# ProPrj_Volt_Meter_25_3_25_2025-04-11.net
KiCad netlist of a schematic drawn in EasyEDA Pro
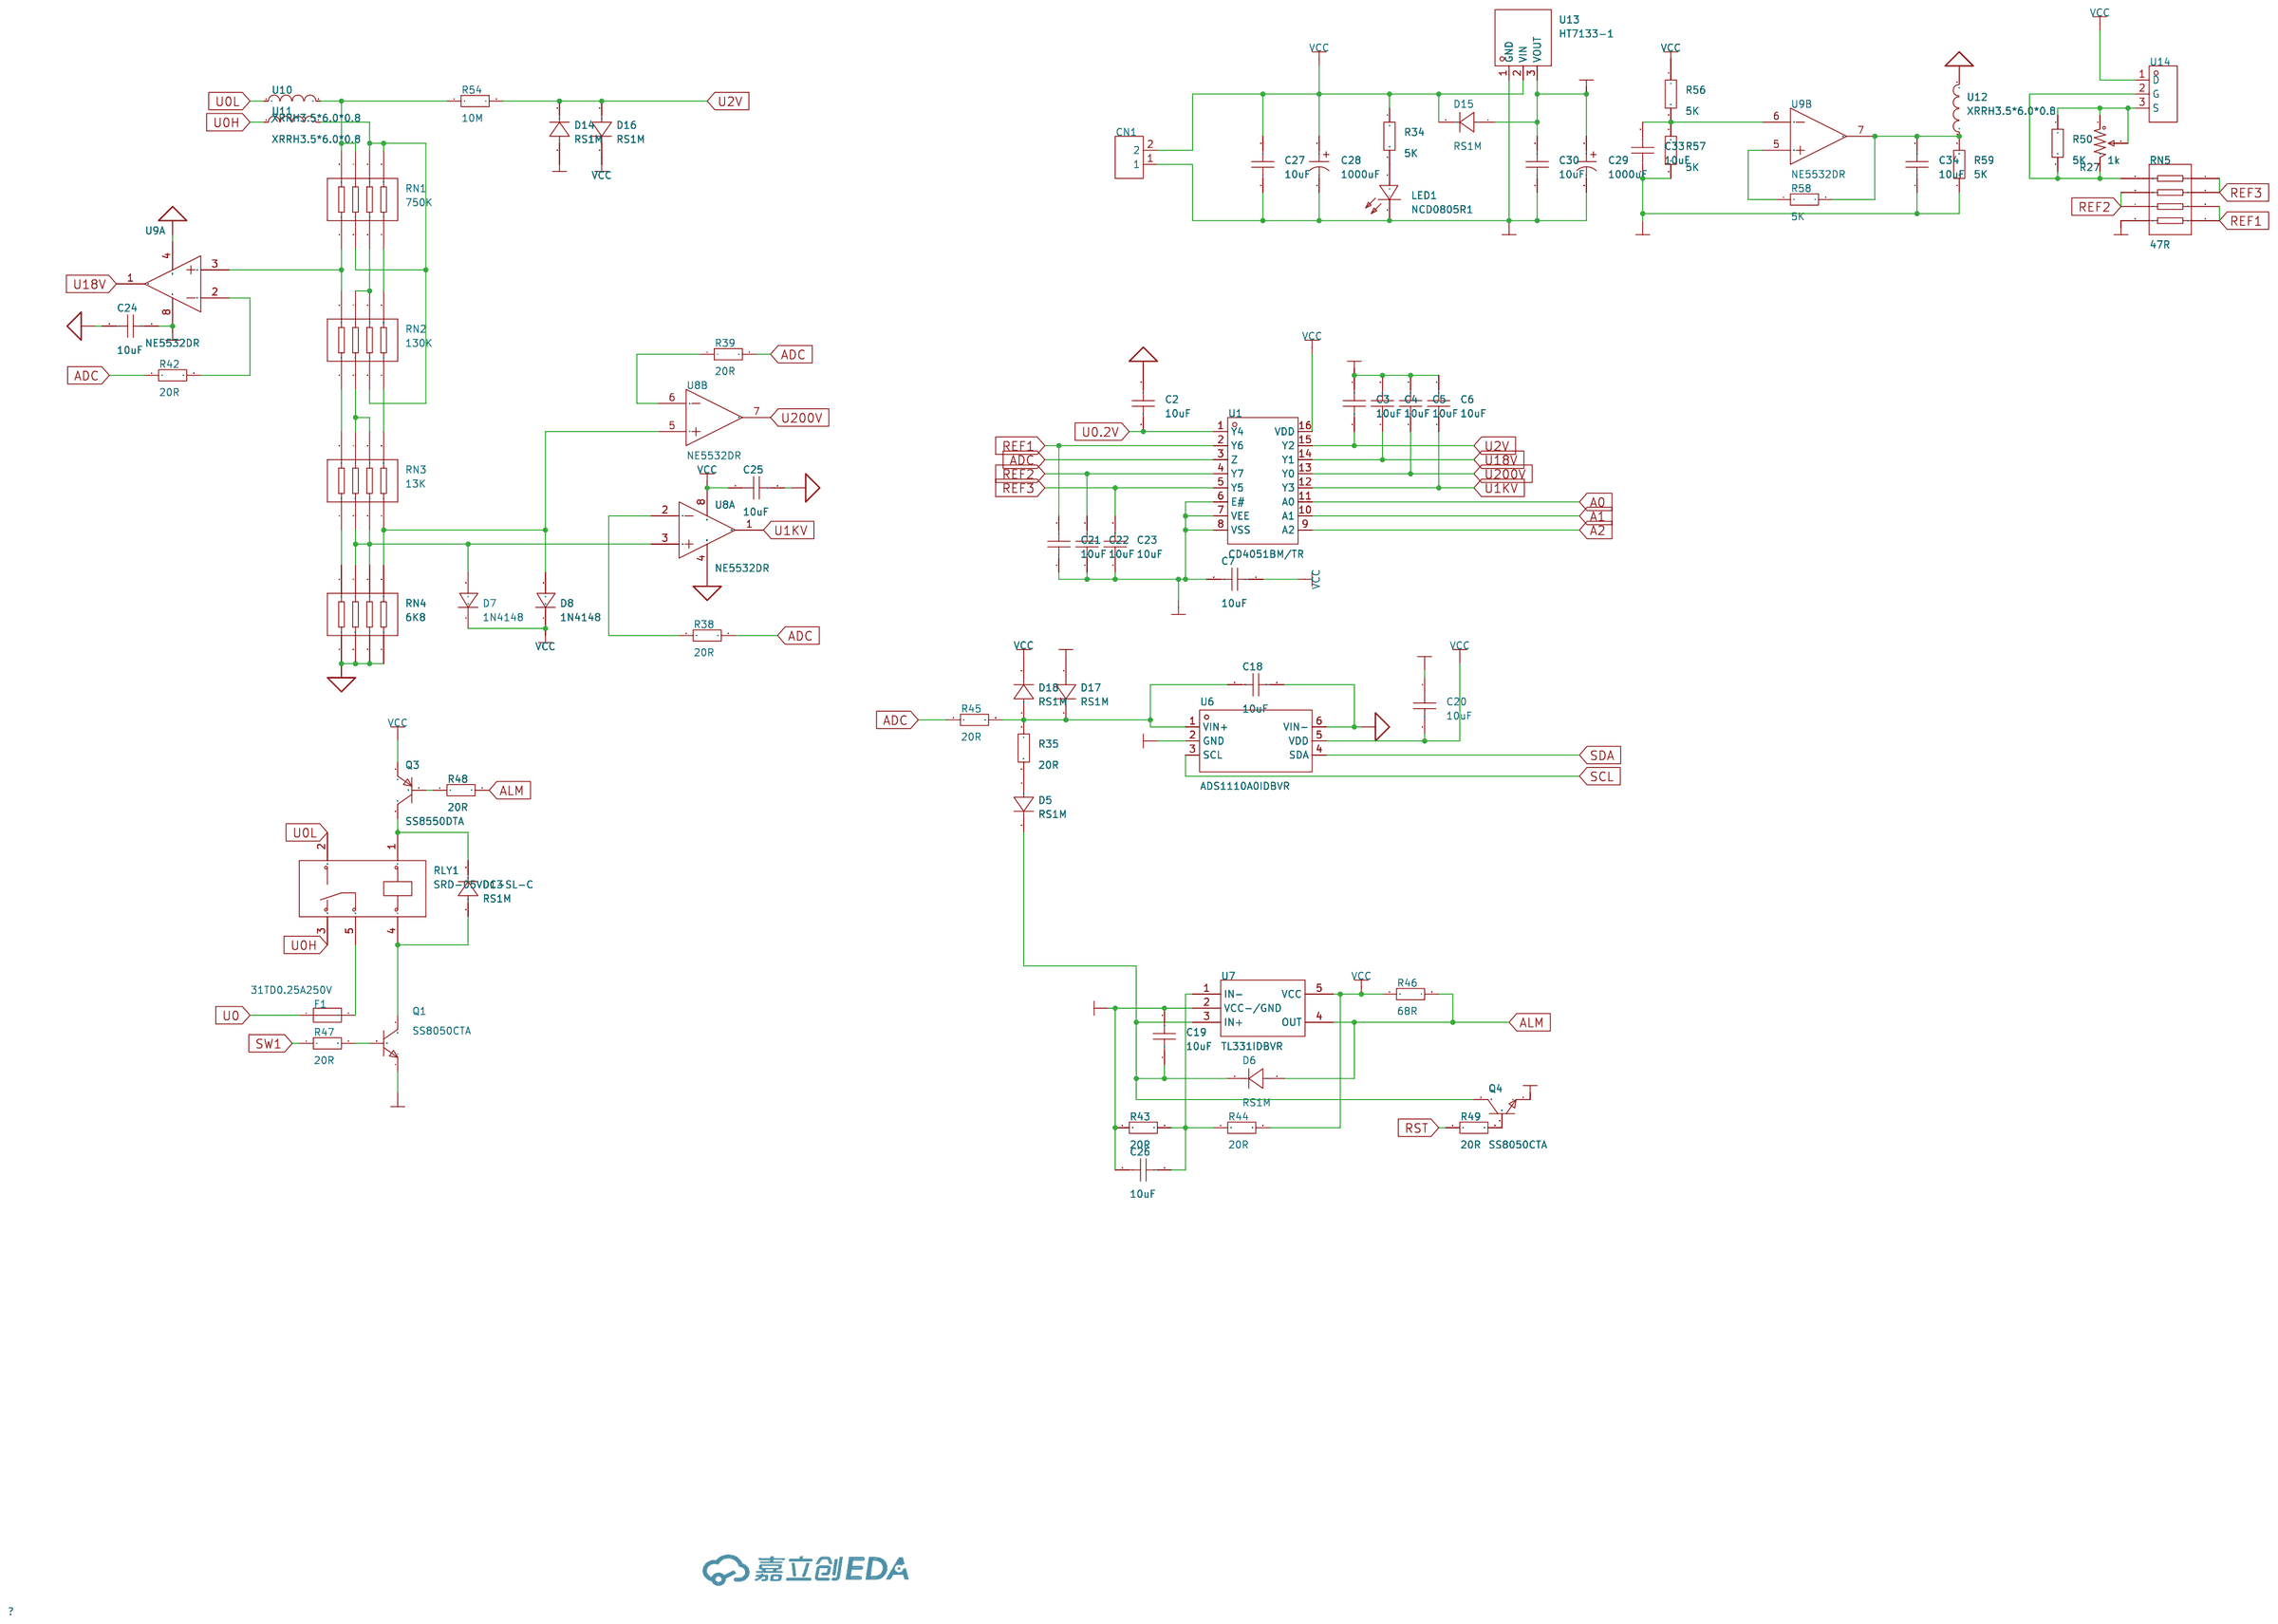
[diagram p0: P1]
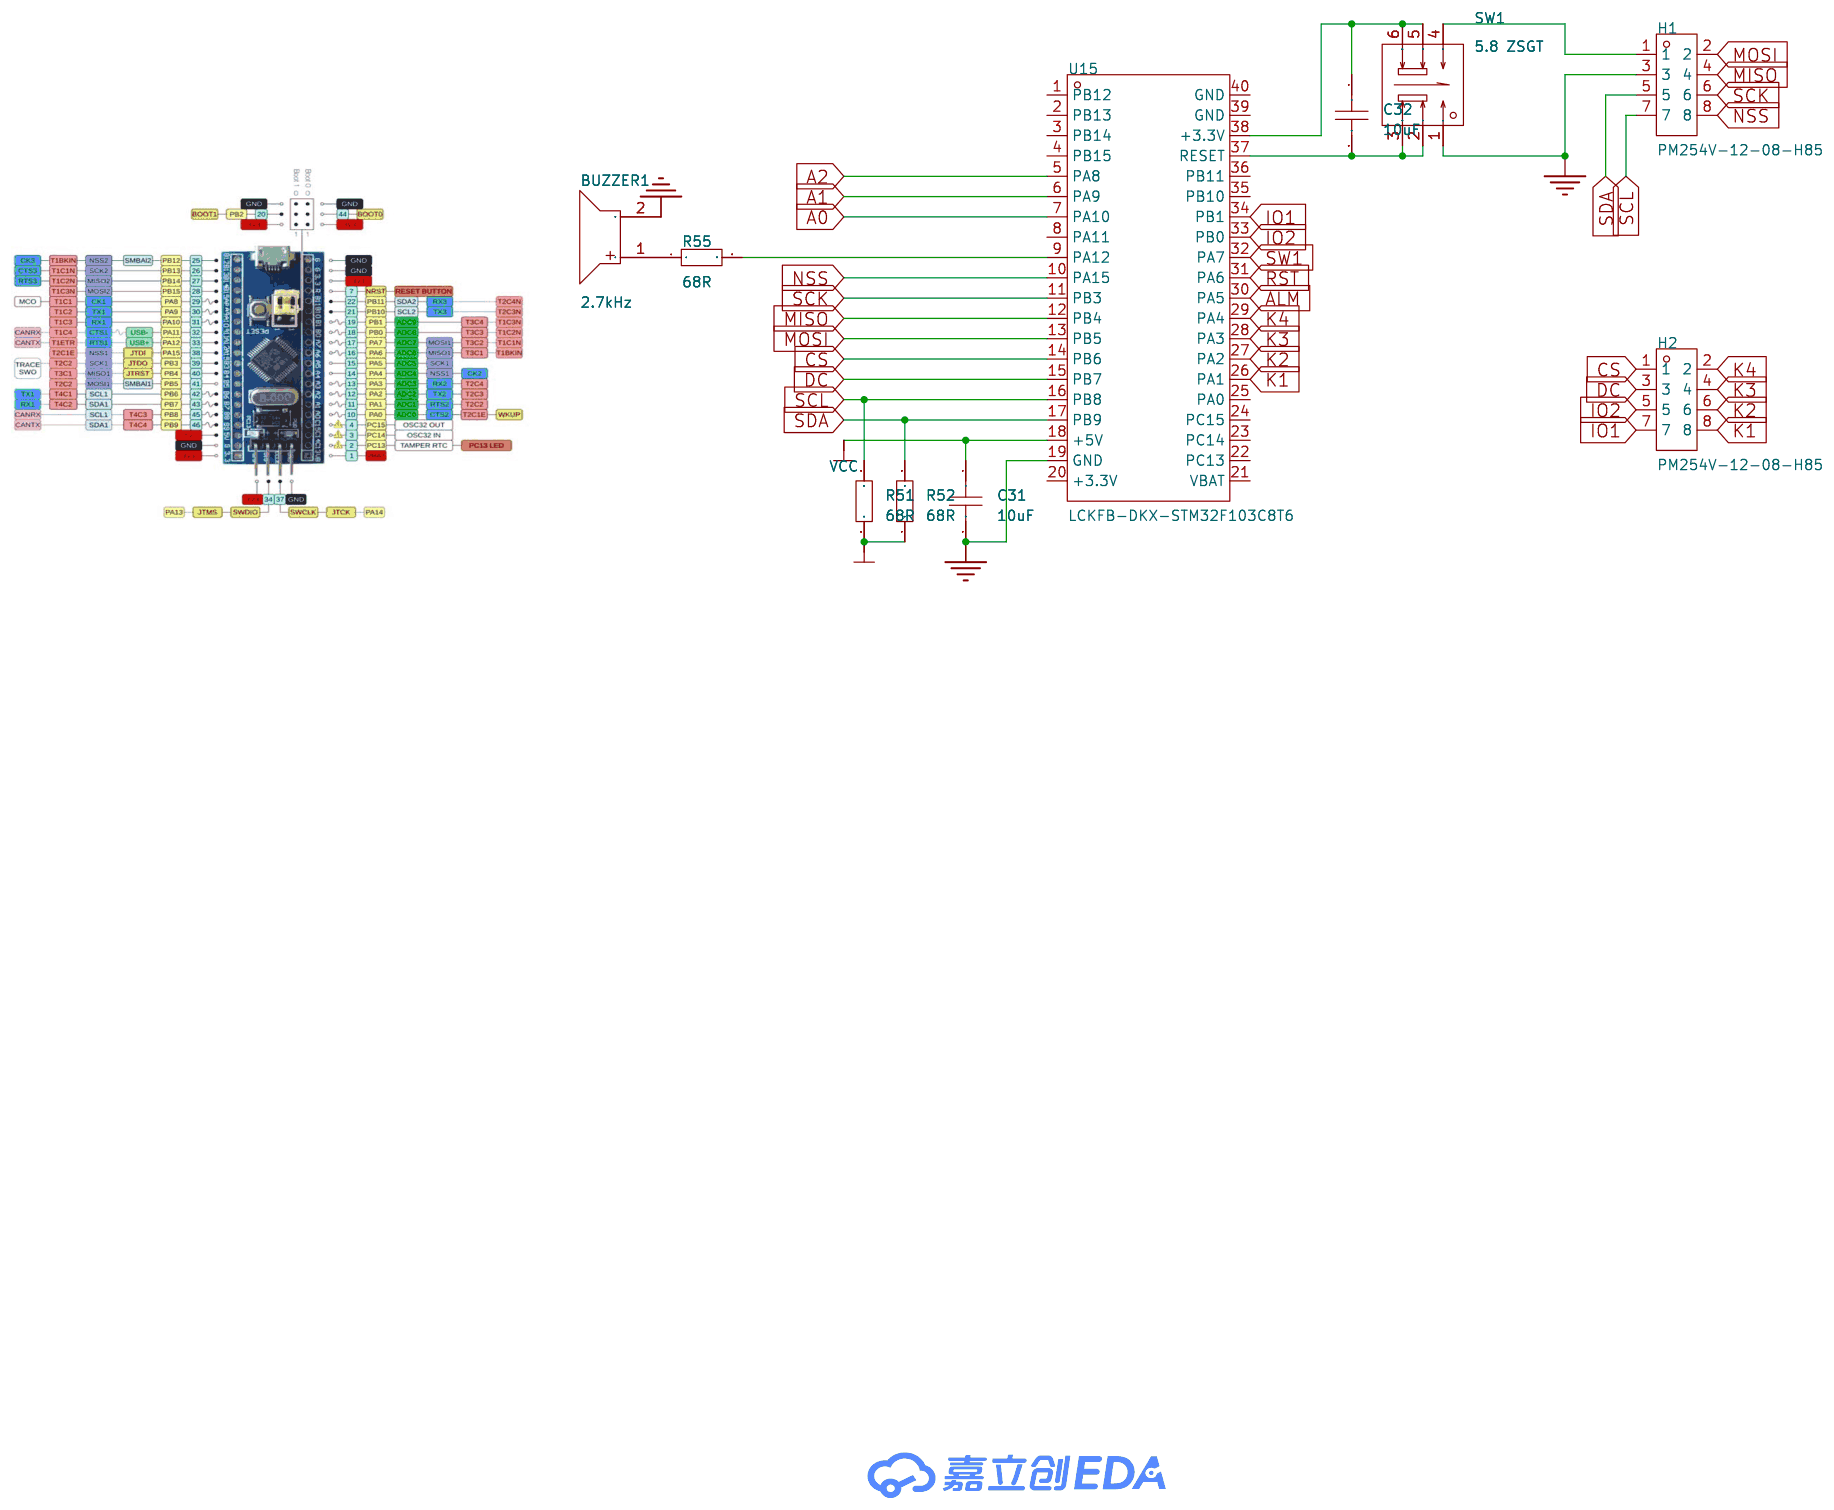
[diagram p1: P2]

(export (version "E")
  (design (tool "Eeschema 10.0.6"))
  (components
    (comp (ref "C2")
      (value "10uF")
      (footprint "easyedapro:C1206")
      (description "容值:10uF;精度:±10%;额定电压:50V;温度系数:X5R;")
      (fields
        (field (name "Manufacturer Part") "HGC1206R5106K500NSPJ")
        (field (name "Manufacturer") "Chinocera(华瓷)")
      )
      (libsource (lib "easyedapro") (part "HGC1206R5106K500NSPJ"))
    )
    (comp (ref "C3")
      (value "10uF")
      (footprint "easyedapro:C1206")
      (description "容值:10uF;精度:±10%;额定电压:50V;温度系数:X5R;")
      (fields
        (field (name "Manufacturer Part") "HGC1206R5106K500NSPJ")
        (field (name "Manufacturer") "Chinocera(华瓷)")
      )
      (libsource (lib "easyedapro") (part "HGC1206R5106K500NSPJ"))
    )
    (comp (ref "C4")
      (value "10uF")
      (footprint "easyedapro:C1206")
      (description "容值:10uF;精度:±10%;额定电压:50V;温度系数:X5R;")
      (fields
        (field (name "Manufacturer Part") "HGC1206R5106K500NSPJ")
        (field (name "Manufacturer") "Chinocera(华瓷)")
      )
      (libsource (lib "easyedapro") (part "HGC1206R5106K500NSPJ"))
    )
    (comp (ref "C5")
      (value "10uF")
      (footprint "easyedapro:C1206")
      (description "容值:10uF;精度:±10%;额定电压:50V;温度系数:X5R;")
      (fields
        (field (name "Manufacturer Part") "HGC1206R5106K500NSPJ")
        (field (name "Manufacturer") "Chinocera(华瓷)")
      )
      (libsource (lib "easyedapro") (part "HGC1206R5106K500NSPJ"))
    )
    (comp (ref "C6")
      (value "10uF")
      (footprint "easyedapro:C1206")
      (description "容值:10uF;精度:±10%;额定电压:50V;温度系数:X5R;")
      (fields
        (field (name "Manufacturer Part") "HGC1206R5106K500NSPJ")
        (field (name "Manufacturer") "Chinocera(华瓷)")
      )
      (libsource (lib "easyedapro") (part "HGC1206R5106K500NSPJ"))
    )
    (comp (ref "C7")
      (value "10uF")
      (footprint "easyedapro:C1206")
      (description "容值:10uF;精度:±10%;额定电压:50V;温度系数:X5R;")
      (fields
        (field (name "Manufacturer Part") "HGC1206R5106K500NSPJ")
        (field (name "Manufacturer") "Chinocera(华瓷)")
      )
      (libsource (lib "easyedapro") (part "HGC1206R5106K500NSPJ"))
    )
    (comp (ref "C18")
      (value "10uF")
      (footprint "easyedapro:C1206")
      (description "容值:10uF;精度:±10%;额定电压:50V;温度系数:X5R;")
      (fields
        (field (name "Manufacturer Part") "HGC1206R5106K500NSPJ")
        (field (name "Manufacturer") "Chinocera(华瓷)")
      )
      (libsource (lib "easyedapro") (part "HGC1206R5106K500NSPJ"))
    )
    (comp (ref "C19")
      (value "10uF")
      (footprint "easyedapro:C1206")
      (description "容值:10uF;精度:±10%;额定电压:50V;温度系数:X5R;")
      (fields
        (field (name "Manufacturer Part") "HGC1206R5106K500NSPJ")
        (field (name "Manufacturer") "Chinocera(华瓷)")
      )
      (libsource (lib "easyedapro") (part "HGC1206R5106K500NSPJ"))
    )
    (comp (ref "C20")
      (value "10uF")
      (footprint "easyedapro:C1206")
      (description "容值:10uF;精度:±10%;额定电压:50V;温度系数:X5R;")
      (fields
        (field (name "Manufacturer Part") "HGC1206R5106K500NSPJ")
        (field (name "Manufacturer") "Chinocera(华瓷)")
      )
      (libsource (lib "easyedapro") (part "HGC1206R5106K500NSPJ"))
    )
    (comp (ref "C21")
      (value "10uF")
      (footprint "easyedapro:C1206")
      (description "容值:10uF;精度:±10%;额定电压:50V;温度系数:X5R;")
      (fields
        (field (name "Manufacturer Part") "HGC1206R5106K500NSPJ")
        (field (name "Manufacturer") "Chinocera(华瓷)")
      )
      (libsource (lib "easyedapro") (part "HGC1206R5106K500NSPJ"))
    )
    (comp (ref "C22")
      (value "10uF")
      (footprint "easyedapro:C1206")
      (description "容值:10uF;精度:±10%;额定电压:50V;温度系数:X5R;")
      (fields
        (field (name "Manufacturer Part") "HGC1206R5106K500NSPJ")
        (field (name "Manufacturer") "Chinocera(华瓷)")
      )
      (libsource (lib "easyedapro") (part "HGC1206R5106K500NSPJ"))
    )
    (comp (ref "C23")
      (value "10uF")
      (footprint "easyedapro:C1206")
      (description "容值:10uF;精度:±10%;额定电压:50V;温度系数:X5R;")
      (fields
        (field (name "Manufacturer Part") "HGC1206R5106K500NSPJ")
        (field (name "Manufacturer") "Chinocera(华瓷)")
      )
      (libsource (lib "easyedapro") (part "HGC1206R5106K500NSPJ"))
    )
    (comp (ref "C24")
      (value "10uF")
      (footprint "easyedapro:C1206")
      (description "容值:10uF;精度:±10%;额定电压:50V;温度系数:X5R;")
      (fields
        (field (name "Manufacturer Part") "HGC1206R5106K500NSPJ")
        (field (name "Manufacturer") "Chinocera(华瓷)")
      )
      (libsource (lib "easyedapro") (part "HGC1206R5106K500NSPJ"))
    )
    (comp (ref "C25")
      (value "10uF")
      (footprint "easyedapro:C1206")
      (description "容值:10uF;精度:±10%;额定电压:50V;温度系数:X5R;")
      (fields
        (field (name "Manufacturer Part") "HGC1206R5106K500NSPJ")
        (field (name "Manufacturer") "Chinocera(华瓷)")
      )
      (libsource (lib "easyedapro") (part "HGC1206R5106K500NSPJ"))
    )
    (comp (ref "C26")
      (value "10uF")
      (footprint "easyedapro:C1206")
      (description "容值:10uF;精度:±10%;额定电压:50V;温度系数:X5R;")
      (fields
        (field (name "Manufacturer Part") "HGC1206R5106K500NSPJ")
        (field (name "Manufacturer") "Chinocera(华瓷)")
      )
      (libsource (lib "easyedapro") (part "HGC1206R5106K500NSPJ"))
    )
    (comp (ref "C27")
      (value "10uF")
      (footprint "easyedapro:C1206")
      (description "容值:10uF;精度:±10%;额定电压:50V;温度系数:X5R;")
      (fields
        (field (name "Manufacturer Part") "HGC1206R5106K500NSPJ")
        (field (name "Manufacturer") "Chinocera(华瓷)")
      )
      (libsource (lib "easyedapro") (part "HGC1206R5106K500NSPJ"))
    )
    (comp (ref "C28")
      (value "1000uF")
      (footprint "easyedapro:CAP-TH_BD10.0-P5.00-D0.6-FD")
      (description "容值:1000uF;额定电压:35V;")
      (fields
        (field (name "Manufacturer Part") "CD288108M1V1020VFL")
        (field (name "Manufacturer") "HRK(鸿瑞凯)")
      )
      (libsource (lib "easyedapro") (part "CD288108M1V1020VFL"))
    )
    (comp (ref "C29")
      (value "1000uF")
      (footprint "easyedapro:CAP-TH_BD10.0-P5.00-D0.6-FD")
      (description "容值:1000uF;额定电压:35V;")
      (fields
        (field (name "Manufacturer Part") "CD288108M1V1020VFL")
        (field (name "Manufacturer") "HRK(鸿瑞凯)")
      )
      (libsource (lib "easyedapro") (part "CD288108M1V1020VFL"))
    )
    (comp (ref "C30")
      (value "10uF")
      (footprint "easyedapro:C1206")
      (description "容值:10uF;精度:±10%;额定电压:50V;温度系数:X5R;")
      (fields
        (field (name "Manufacturer Part") "HGC1206R5106K500NSPJ")
        (field (name "Manufacturer") "Chinocera(华瓷)")
      )
      (libsource (lib "easyedapro") (part "HGC1206R5106K500NSPJ"))
    )
    (comp (ref "C33")
      (value "10uF")
      (footprint "easyedapro:C1206")
      (description "容值:10uF;精度:±10%;额定电压:50V;温度系数:X5R;")
      (fields
        (field (name "Manufacturer Part") "HGC1206R5106K500NSPJ")
        (field (name "Manufacturer") "Chinocera(华瓷)")
      )
      (libsource (lib "easyedapro") (part "HGC1206R5106K500NSPJ"))
    )
    (comp (ref "C34")
      (value "10uF")
      (footprint "easyedapro:C1206")
      (description "容值:10uF;精度:±10%;额定电压:50V;温度系数:X5R;")
      (fields
        (field (name "Manufacturer Part") "HGC1206R5106K500NSPJ")
        (field (name "Manufacturer") "Chinocera(华瓷)")
      )
      (libsource (lib "easyedapro") (part "HGC1206R5106K500NSPJ"))
    )
    (comp (ref "CN1")
      (value "WAFER-XH254Z-2A")
      (footprint "easyedapro:CONN-TH_2P-P2.50_XH-2A_3045048")
      (description "插针结构:1x2P;间距:2.54mm;安装方式:直插;参考系列:XH;总PIN数:2P;排数:1;每排PIN数:2;额定电流:3A;工作温度范围:-25°C~+85°C;")
      (fields (field (name "Manufacturer") "HANBO(汉博)"))
      (libsource (lib "easyedapro") (part "WAFER-XH254Z-2A"))
    )
    (comp (ref "D5")
      (value "RS1M")
      (footprint "easyedapro:SMA_L4.3-W2.6-LS5.2-FD")
      (description "二极管配置:-;正向压降(Vf):1.3V@1A;直流反向耐压(Vr):1kV;平均整流电流(Io):1A;反向恢复时间(trr):500ns;")
      (fields (field (name "Manufacturer") "onsemi(安森美)"))
      (libsource (lib "easyedapro") (part "RS1M_C84573"))
    )
    (comp (ref "D6")
      (value "RS1M")
      (footprint "easyedapro:SMA_L4.3-W2.6-LS5.2-FD")
      (description "二极管配置:-;正向压降(Vf):1.3V@1A;直流反向耐压(Vr):1kV;平均整流电流(Io):1A;反向恢复时间(trr):500ns;")
      (fields (field (name "Manufacturer") "onsemi(安森美)"))
      (libsource (lib "easyedapro") (part "RS1M_C84573"))
    )
    (comp (ref "D7")
      (value "1N4148")
      (footprint "easyedapro:DO-35_BD2.0-L4.2-P8.20-D0.5-RD")
      (description "二极管配置:-;正向压降(Vf):1V@10mA;直流反向耐压(Vr):75V;整流电流:150mA;反向恢复时间(Trr):4ns;")
      (fields (field (name "Manufacturer") "LGE(鲁光)"))
      (libsource (lib "easyedapro") (part "1N4148_C402212"))
    )
    (comp (ref "D8")
      (value "1N4148")
      (footprint "easyedapro:DO-35_BD2.0-L4.2-P8.20-D0.5-RD")
      (description "二极管配置:-;正向压降(Vf):1V@10mA;直流反向耐压(Vr):75V;整流电流:150mA;反向恢复时间(Trr):4ns;")
      (fields (field (name "Manufacturer") "LGE(鲁光)"))
      (libsource (lib "easyedapro") (part "1N4148_C402212"))
    )
    (comp (ref "D13")
      (value "RS1M")
      (footprint "easyedapro:SMA_L4.3-W2.6-LS5.2-FD")
      (description "二极管配置:-;正向压降(Vf):1.3V@1A;直流反向耐压(Vr):1kV;平均整流电流(Io):1A;反向恢复时间(trr):500ns;")
      (fields (field (name "Manufacturer") "onsemi(安森美)"))
      (libsource (lib "easyedapro") (part "RS1M_C84573"))
    )
    (comp (ref "D14")
      (value "RS1M")
      (footprint "easyedapro:SMA_L4.3-W2.6-LS5.2-FD")
      (description "二极管配置:-;正向压降(Vf):1.3V@1A;直流反向耐压(Vr):1kV;平均整流电流(Io):1A;反向恢复时间(trr):500ns;")
      (fields (field (name "Manufacturer") "onsemi(安森美)"))
      (libsource (lib "easyedapro") (part "RS1M_C84573"))
    )
    (comp (ref "D15")
      (value "RS1M")
      (footprint "easyedapro:SMA_L4.3-W2.6-LS5.2-FD")
      (description "二极管配置:-;正向压降(Vf):1.3V@1A;直流反向耐压(Vr):1kV;平均整流电流(Io):1A;反向恢复时间(trr):500ns;")
      (fields (field (name "Manufacturer") "onsemi(安森美)"))
      (libsource (lib "easyedapro") (part "RS1M_C84573"))
    )
    (comp (ref "D16")
      (value "RS1M")
      (footprint "easyedapro:SMA_L4.3-W2.6-LS5.2-FD")
      (description "二极管配置:-;正向压降(Vf):1.3V@1A;直流反向耐压(Vr):1kV;平均整流电流(Io):1A;反向恢复时间(trr):500ns;")
      (fields (field (name "Manufacturer") "onsemi(安森美)"))
      (libsource (lib "easyedapro") (part "RS1M_C84573"))
    )
    (comp (ref "D17")
      (value "RS1M")
      (footprint "easyedapro:SMA_L4.3-W2.6-LS5.2-FD")
      (description "二极管配置:-;正向压降(Vf):1.3V@1A;直流反向耐压(Vr):1kV;平均整流电流(Io):1A;反向恢复时间(trr):500ns;")
      (fields (field (name "Manufacturer") "onsemi(安森美)"))
      (libsource (lib "easyedapro") (part "RS1M_C84573"))
    )
    (comp (ref "D18")
      (value "RS1M")
      (footprint "easyedapro:SMA_L4.3-W2.6-LS5.2-FD")
      (description "二极管配置:-;正向压降(Vf):1.3V@1A;直流反向耐压(Vr):1kV;平均整流电流(Io):1A;反向恢复时间(trr):500ns;")
      (fields (field (name "Manufacturer") "onsemi(安森美)"))
      (libsource (lib "easyedapro") (part "RS1M_C84573"))
    )
    (comp (ref "F1")
      (value "31TD0.25A250V")
      (footprint "easyedapro:FUSE-TH_BD4.0-L11.0-P15.00-D0.6")
      (description "类型:玻璃管保险丝;额定电流:3.15A;")
      (fields (field (name "Manufacturer") "Hongda(泓达)"))
      (libsource (lib "easyedapro") (part "31TD3.15A250V"))
    )
    (comp (ref "LED1")
      (value "NCD0805R1")
      (footprint "easyedapro:LED0805-R-RD")
      (fields (field (name "Manufacturer") "国星光电"))
      (libsource (lib "easyedapro") (part "FC-2012HRK-620D"))
    )
    (comp (ref "Q1")
      (value "SS8050CTA")
      (footprint "easyedapro:TO-92-3_L4.8-W3.7-P2.54-L")
      (description "晶体管类型:NPN;集电极电流(Ic):1.5A;集射极击穿电压(Vceo):25V;功率(Pd):1W;直流电流增益(hFE@Ic,Vce):45@5mA,1V;")
      (fields (field (name "Manufacturer") "onsemi(安森美)"))
      (libsource (lib "easyedapro") (part "SS8050CTA"))
    )
    (comp (ref "Q3")
      (value "SS8550DTA")
      (footprint "easyedapro:TO-92-3_L4.8-W3.7-P2.54-L")
      (description "晶体管类型:PNP;集电极电流(Ic):1.5A;集射极击穿电压(Vceo):25V;功率(Pd):2W;直流电流增益(hFE@Ic,Vce):40@800mA,1V;")
      (fields (field (name "Manufacturer") "onsemi(安森美)"))
      (libsource (lib "easyedapro") (part "SS8550DTA"))
    )
    (comp (ref "Q4")
      (value "SS8050CTA")
      (footprint "easyedapro:TO-92-3_L4.8-W3.7-P2.54-L")
      (description "晶体管类型:NPN;集电极电流(Ic):1.5A;集射极击穿电压(Vceo):25V;功率(Pd):1W;直流电流增益(hFE@Ic,Vce):45@5mA,1V;")
      (fields (field (name "Manufacturer") "onsemi(安森美)"))
      (libsource (lib "easyedapro") (part "SS8050CTA"))
    )
    (comp (ref "R27")
      (value "1k")
      (footprint "easyedapro:RES-ADJ-SMD_RM065-V1")
      (description "阻值:10kΩ;精度:±25%;功率:100mW;")
      (fields (field (name "Manufacturer Part") "RM065-103(10K)") (field (name "Manufacturer") "BOCHEN(博晨)"))
      (libsource (lib "easyedapro") (part "RM065-103(10K)"))
    )
    (comp (ref "R34")
      (value "5K")
      (footprint "easyedapro:R1206")
      (description "电阻类型:厚膜电阻;阻值:4.7kΩ;精度:±1%;功率:250mW;最大工作电压:200V;温度系数:±100ppm/°C;")
      (fields
        (field (name "Manufacturer Part") "1206W4F4701T5E")
        (field (name "Manufacturer") "UNI-ROYAL(厚声)")
      )
      (libsource (lib "easyedapro") (part "1206W4F4701T5E"))
    )
    (comp (ref "R35")
      (value "20R")
      (footprint "easyedapro:R1206")
      (description "电阻类型:厚膜电阻;阻值:4.7kΩ;精度:±1%;功率:250mW;最大工作电压:200V;温度系数:±100ppm/°C;")
      (fields
        (field (name "Manufacturer Part") "1206W4F4701T5E")
        (field (name "Manufacturer") "UNI-ROYAL(厚声)")
      )
      (libsource (lib "easyedapro") (part "1206W4F4701T5E"))
    )
    (comp (ref "R38")
      (value "20R")
      (footprint "easyedapro:R1206")
      (description "电阻类型:厚膜电阻;阻值:4.7kΩ;精度:±1%;功率:250mW;最大工作电压:200V;温度系数:±100ppm/°C;")
      (fields
        (field (name "Manufacturer Part") "1206W4F4701T5E")
        (field (name "Manufacturer") "UNI-ROYAL(厚声)")
      )
      (libsource (lib "easyedapro") (part "1206W4F4701T5E"))
    )
    (comp (ref "R39")
      (value "20R")
      (footprint "easyedapro:R1206")
      (description "电阻类型:厚膜电阻;阻值:4.7kΩ;精度:±1%;功率:250mW;最大工作电压:200V;温度系数:±100ppm/°C;")
      (fields
        (field (name "Manufacturer Part") "1206W4F4701T5E")
        (field (name "Manufacturer") "UNI-ROYAL(厚声)")
      )
      (libsource (lib "easyedapro") (part "1206W4F4701T5E"))
    )
    (comp (ref "R42")
      (value "20R")
      (footprint "easyedapro:R1206")
      (description "电阻类型:厚膜电阻;阻值:4.7kΩ;精度:±1%;功率:250mW;最大工作电压:200V;温度系数:±100ppm/°C;")
      (fields
        (field (name "Manufacturer Part") "1206W4F4701T5E")
        (field (name "Manufacturer") "UNI-ROYAL(厚声)")
      )
      (libsource (lib "easyedapro") (part "1206W4F4701T5E"))
    )
    (comp (ref "R43")
      (value "20R")
      (footprint "easyedapro:R1206")
      (description "电阻类型:厚膜电阻;阻值:4.7kΩ;精度:±1%;功率:250mW;最大工作电压:200V;温度系数:±100ppm/°C;")
      (fields
        (field (name "Manufacturer Part") "1206W4F4701T5E")
        (field (name "Manufacturer") "UNI-ROYAL(厚声)")
      )
      (libsource (lib "easyedapro") (part "1206W4F4701T5E"))
    )
    (comp (ref "R44")
      (value "20R")
      (footprint "easyedapro:R1206")
      (description "电阻类型:厚膜电阻;阻值:4.7kΩ;精度:±1%;功率:250mW;最大工作电压:200V;温度系数:±100ppm/°C;")
      (fields
        (field (name "Manufacturer Part") "1206W4F4701T5E")
        (field (name "Manufacturer") "UNI-ROYAL(厚声)")
      )
      (libsource (lib "easyedapro") (part "1206W4F4701T5E"))
    )
    (comp (ref "R45")
      (value "20R")
      (footprint "easyedapro:R1206")
      (description "电阻类型:厚膜电阻;阻值:4.7kΩ;精度:±1%;功率:250mW;最大工作电压:200V;温度系数:±100ppm/°C;")
      (fields
        (field (name "Manufacturer Part") "1206W4F4701T5E")
        (field (name "Manufacturer") "UNI-ROYAL(厚声)")
      )
      (libsource (lib "easyedapro") (part "1206W4F4701T5E"))
    )
    (comp (ref "R46")
      (value "68R")
      (footprint "easyedapro:R1206")
      (description "电阻类型:厚膜电阻;阻值:4.7kΩ;精度:±1%;功率:250mW;最大工作电压:200V;温度系数:±100ppm/°C;")
      (fields
        (field (name "Manufacturer Part") "1206W4F4701T5E")
        (field (name "Manufacturer") "UNI-ROYAL(厚声)")
      )
      (libsource (lib "easyedapro") (part "1206W4F4701T5E"))
    )
    (comp (ref "R47")
      (value "20R")
      (footprint "easyedapro:R1206")
      (description "电阻类型:厚膜电阻;阻值:4.7kΩ;精度:±1%;功率:250mW;最大工作电压:200V;温度系数:±100ppm/°C;")
      (fields
        (field (name "Manufacturer Part") "1206W4F4701T5E")
        (field (name "Manufacturer") "UNI-ROYAL(厚声)")
      )
      (libsource (lib "easyedapro") (part "1206W4F4701T5E"))
    )
    (comp (ref "R48")
      (value "20R")
      (footprint "easyedapro:R1206")
      (description "电阻类型:厚膜电阻;阻值:4.7kΩ;精度:±1%;功率:250mW;最大工作电压:200V;温度系数:±100ppm/°C;")
      (fields
        (field (name "Manufacturer Part") "1206W4F4701T5E")
        (field (name "Manufacturer") "UNI-ROYAL(厚声)")
      )
      (libsource (lib "easyedapro") (part "1206W4F4701T5E"))
    )
    (comp (ref "R49")
      (value "20R")
      (footprint "easyedapro:R1206")
      (description "电阻类型:厚膜电阻;阻值:4.7kΩ;精度:±1%;功率:250mW;最大工作电压:200V;温度系数:±100ppm/°C;")
      (fields
        (field (name "Manufacturer Part") "1206W4F4701T5E")
        (field (name "Manufacturer") "UNI-ROYAL(厚声)")
      )
      (libsource (lib "easyedapro") (part "1206W4F4701T5E"))
    )
    (comp (ref "R50")
      (value "5K")
      (footprint "easyedapro:R1206")
      (description "电阻类型:厚膜电阻;阻值:4.7kΩ;精度:±1%;功率:250mW;最大工作电压:200V;温度系数:±100ppm/°C;")
      (fields
        (field (name "Manufacturer Part") "1206W4F4701T5E")
        (field (name "Manufacturer") "UNI-ROYAL(厚声)")
      )
      (libsource (lib "easyedapro") (part "1206W4F4701T5E"))
    )
    (comp (ref "R54")
      (value "10M")
      (footprint "easyedapro:RES-TH_BD3.3-L9.0-P13.00-D0.6")
      (description "电阻类型:金属膜电阻;阻值:15kΩ;精度:±1%;功率:1W;温度系数:±50ppm/°C;")
      (fields
        (field (name "Manufacturer Part") "RN1WS15KΩFT/BA1")
        (field (name "Manufacturer") "Tyohm(幸亚电阻)")
      )
      (libsource (lib "easyedapro") (part "RN1WS15KΩFT/BA1"))
    )
    (comp (ref "R56")
      (value "5K")
      (footprint "easyedapro:R1206")
      (description "电阻类型:厚膜电阻;阻值:4.7kΩ;精度:±1%;功率:250mW;最大工作电压:200V;温度系数:±100ppm/°C;")
      (fields
        (field (name "Manufacturer Part") "1206W4F4701T5E")
        (field (name "Manufacturer") "UNI-ROYAL(厚声)")
      )
      (libsource (lib "easyedapro") (part "1206W4F4701T5E"))
    )
    (comp (ref "R57")
      (value "5K")
      (footprint "easyedapro:R1206")
      (description "电阻类型:厚膜电阻;阻值:4.7kΩ;精度:±1%;功率:250mW;最大工作电压:200V;温度系数:±100ppm/°C;")
      (fields
        (field (name "Manufacturer Part") "1206W4F4701T5E")
        (field (name "Manufacturer") "UNI-ROYAL(厚声)")
      )
      (libsource (lib "easyedapro") (part "1206W4F4701T5E"))
    )
    (comp (ref "R58")
      (value "5K")
      (footprint "easyedapro:R1206")
      (description "电阻类型:厚膜电阻;阻值:4.7kΩ;精度:±1%;功率:250mW;最大工作电压:200V;温度系数:±100ppm/°C;")
      (fields
        (field (name "Manufacturer Part") "1206W4F4701T5E")
        (field (name "Manufacturer") "UNI-ROYAL(厚声)")
      )
      (libsource (lib "easyedapro") (part "1206W4F4701T5E"))
    )
    (comp (ref "R59")
      (value "5K")
      (footprint "easyedapro:R1206")
      (description "电阻类型:厚膜电阻;阻值:4.7kΩ;精度:±1%;功率:250mW;最大工作电压:200V;温度系数:±100ppm/°C;")
      (fields
        (field (name "Manufacturer Part") "1206W4F4701T5E")
        (field (name "Manufacturer") "UNI-ROYAL(厚声)")
      )
      (libsource (lib "easyedapro") (part "1206W4F4701T5E"))
    )
    (comp (ref "RLY1")
      (value "SRD-05VDC-SL-C")
      (footprint "easyedapro:RELAY-TH_SRD-XXVDC-XL-C")
      (description "线圈电压:5V;触点形式:一组转换:1C(单刀双掷-转换);触点容量(电阻负载):-;最大切换电压:250V@AC;最大切换电流:15A;")
      (fields (field (name "Manufacturer") "松乐"))
      (libsource (lib "easyedapro") (part "SRD-05VDC-SL-C"))
    )
    (comp (ref "RN1")
      (value "750K")
      (footprint "easyedapro:RES-ARRAY-SMD_0603-8P-L3.2-W1.6-BL")
      (description "电阻器数:4;阻值:10kΩ;精度:±5%;单个元件功率:62.5mW;温度系数:±200ppm/°C;")
      (fields
        (field (name "Manufacturer Part") "4D03WGJ0103T5E")
        (field (name "Manufacturer") "UNI-ROYAL(厚声)")
      )
      (libsource (lib "easyedapro") (part "4D03WGJ0103T5E"))
    )
    (comp (ref "RN2")
      (value "130K")
      (footprint "easyedapro:RES-ARRAY-SMD_0603-8P-L3.2-W1.6-BL")
      (description "电阻器数:4;阻值:10kΩ;精度:±5%;单个元件功率:62.5mW;温度系数:±200ppm/°C;")
      (fields
        (field (name "Manufacturer Part") "4D03WGJ0103T5E")
        (field (name "Manufacturer") "UNI-ROYAL(厚声)")
      )
      (libsource (lib "easyedapro") (part "4D03WGJ0103T5E"))
    )
    (comp (ref "RN3")
      (value "13K")
      (footprint "easyedapro:RES-ARRAY-SMD_0603-8P-L3.2-W1.6-BL")
      (description "电阻器数:4;阻值:10kΩ;精度:±5%;单个元件功率:62.5mW;温度系数:±200ppm/°C;")
      (fields
        (field (name "Manufacturer Part") "4D03WGJ0103T5E")
        (field (name "Manufacturer") "UNI-ROYAL(厚声)")
      )
      (libsource (lib "easyedapro") (part "4D03WGJ0103T5E"))
    )
    (comp (ref "RN4")
      (value "6K8")
      (footprint "easyedapro:RES-ARRAY-SMD_0603-8P-L3.2-W1.6-BL")
      (description "电阻器数:4;阻值:10kΩ;精度:±5%;单个元件功率:62.5mW;温度系数:±200ppm/°C;")
      (fields
        (field (name "Manufacturer Part") "4D03WGJ0103T5E")
        (field (name "Manufacturer") "UNI-ROYAL(厚声)")
      )
      (libsource (lib "easyedapro") (part "4D03WGJ0103T5E"))
    )
    (comp (ref "RN5")
      (value "47R")
      (footprint "easyedapro:RES-ARRAY-SMD_0603-8P-L3.2-W1.6-BL")
      (description "电阻器数:4;阻值:10kΩ;精度:±5%;单个元件功率:62.5mW;温度系数:±200ppm/°C;")
      (fields
        (field (name "Manufacturer Part") "4D03WGJ0103T5E")
        (field (name "Manufacturer") "UNI-ROYAL(厚声)")
      )
      (libsource (lib "easyedapro") (part "4D03WGJ0103T5E"))
    )
    (comp (ref "U1")
      (value "CD4051BM/TR")
      (footprint "easyedapro:SOP-16_L9.9-W3.9-P1.27-LS6.1-BL")
      (description "开关电路:单刀八掷(SP8T);通道数:8;导通电阻(Ron@VCC):60Ω;")
      (fields (field (name "Manufacturer") "HGSEMI(华冠)"))
      (libsource (lib "easyedapro") (part "CD4051BM/TR"))
    )
    (comp (ref "U6")
      (value "ADS1110A0IDBVR")
      (footprint "easyedapro:SOT-23-6_L2.9-W1.6-P0.95-LS2.8-BR")
      (description "接口:I2C;电源电压:2.7V~5.5V;采样率:240Hz;分辨率:16位;")
      (fields (field (name "Manufacturer") "TI(德州仪器)"))
      (libsource (lib "easyedapro") (part "ADS1110A0IDBVR"))
    )
    (comp (ref "U7")
      (value "TL331IDBVR")
      (footprint "easyedapro:SOT-23-5_L3.0-W1.7-P0.95-LS2.8-BR")
      (description "输入失调电压(Vos):5mV;输入偏置电流(Ib):250nA;轨到轨:-;")
      (fields (field (name "Manufacturer") "TI(德州仪器)"))
      (libsource (lib "easyedapro") (part "TL331IDBVR"))
    )
    (comp (ref "U8")
      (value "NE5532DR")
      (footprint "easyedapro:SOIC-8_L4.9-W3.9-P1.27-LS6.0-BL")
      (description "放大器数:双路;增益带宽积(GBP):10MHz;输入偏置电流(Ib):200nA;压摆率(SR):9V/us;带宽(-3db):-;")
      (fields (field (name "Manufacturer") "TI(德州仪器)"))
      (libsource (lib "easyedapro") (part "NE5532DR"))
    )
    (comp (ref "U9")
      (value "NE5532DR")
      (footprint "easyedapro:SOIC-8_L4.9-W3.9-P1.27-LS6.0-BL")
      (description "放大器数:双路;增益带宽积(GBP):10MHz;输入偏置电流(Ib):200nA;压摆率(SR):9V/us;带宽(-3db):-;")
      (fields (field (name "Manufacturer") "TI(德州仪器)"))
      (libsource (lib "easyedapro") (part "NE5532DR"))
    )
    (comp (ref "U10")
      (value "XRRH3.5*6.0*0.8")
      (footprint "easyedapro:IND-TH_BD3.5-L6.0-P10.00-D0.8")
      (description "标称阻抗@测试频率:60Ω@100MHz;")
      (fields (field (name "Manufacturer") "XR(祥如)"))
      (libsource (lib "easyedapro") (part "XRRH3.5*6.0*0.8"))
    )
    (comp (ref "U11")
      (value "XRRH3.5*6.0*0.8")
      (footprint "easyedapro:IND-TH_BD3.5-L6.0-P10.00-D0.8")
      (description "标称阻抗@测试频率:60Ω@100MHz;")
      (fields (field (name "Manufacturer") "XR(祥如)"))
      (libsource (lib "easyedapro") (part "XRRH3.5*6.0*0.8"))
    )
    (comp (ref "U12")
      (value "XRRH3.5*6.0*0.8")
      (footprint "easyedapro:IND-TH_BD3.5-L6.0-P10.00-D0.8")
      (description "标称阻抗@测试频率:60Ω@100MHz;")
      (fields (field (name "Manufacturer") "XR(祥如)"))
      (libsource (lib "easyedapro") (part "XRRH3.5*6.0*0.8"))
    )
    (comp (ref "U13")
      (value "HT7133-1")
      (footprint "easyedapro:SOT-89_L4.5-W2.5-P1.50-LS4.2-BR")
      (description "输出类型:固定;最大输入电压:30V;输出电压:3.3V;输出电流:100mA;电源纹波抑制比(PSRR):-;输出极性:正极;")
      (fields (field (name "Manufacturer") "UMW(友台半导体)"))
      (libsource (lib "easyedapro") (part "HT7133-1_C347181"))
    )
    (comp (ref "U14")
      (value "J175-D26Z")
      (footprint "easyedapro:TO-92-3_L4.9-W3.7-P2.54-L")
      (description "FET类型:P沟道;栅源击穿电压(V(BR)GSS):30V;功率(Pd):350mW;漏源导通电阻(RDS(on)):125Ω;饱和漏源电流(Idss@Vds,Vgs=0):7mA@15V;")
      (fields (field (name "Manufacturer") "onsemi(安森美)"))
      (libsource (lib "easyedapro") (part "J175-D26Z"))
    )
    (comp (ref "BUZZER1")
      (value "2.7kHz")
      (footprint "easyedapro:BUZ-TH_BD9.0-P4.00-D0.6-FD")
      (description "驱动方式:无源(外部驱动);构造类型:电磁式;频率:2.7kHz;声压(SPL):85dB;")
      (fields (field (name "Manufacturer Part") "QMB-09B-03") (field (name "Manufacturer") "华能"))
      (libsource (lib "easyedapro") (part "QMB-09B-03"))
    )
    (comp (ref "C31")
      (value "10uF")
      (footprint "easyedapro:C1206")
      (description "容值:10uF;精度:±10%;额定电压:50V;温度系数:X5R;")
      (fields
        (field (name "Manufacturer Part") "HGC1206R5106K500NSPJ")
        (field (name "Manufacturer") "Chinocera(华瓷)")
      )
      (libsource (lib "easyedapro") (part "HGC1206R5106K500NSPJ"))
    )
    (comp (ref "C32")
      (value "10uF")
      (footprint "easyedapro:C1206")
      (description "容值:10uF;精度:±10%;额定电压:50V;温度系数:X5R;")
      (fields
        (field (name "Manufacturer Part") "HGC1206R5106K500NSPJ")
        (field (name "Manufacturer") "Chinocera(华瓷)")
      )
      (libsource (lib "easyedapro") (part "HGC1206R5106K500NSPJ"))
    )
    (comp (ref "H1")
      (value "PM254V-12-08-H85")
      (footprint "easyedapro:HDR-TH_8P-P2.54-V-F-R2-C4-S2.54")
      (fields (field (name "Manufacturer") "XFCN(兴飞)"))
      (libsource (lib "easyedapro") (part "PM254V-12-08-H85_C2834799"))
    )
    (comp (ref "H2")
      (value "PM254V-12-08-H85")
      (footprint "easyedapro:HDR-TH_8P-P2.54-V-F-R2-C4-S2.54")
      (fields (field (name "Manufacturer") "XFCN(兴飞)"))
      (libsource (lib "easyedapro") (part "PM254V-12-08-H85_C2834799"))
    )
    (comp (ref "R51")
      (value "68R")
      (footprint "easyedapro:R1206")
      (description "电阻类型:厚膜电阻;阻值:4.7kΩ;精度:±1%;功率:250mW;最大工作电压:200V;温度系数:±100ppm/°C;")
      (fields
        (field (name "Manufacturer Part") "1206W4F4701T5E")
        (field (name "Manufacturer") "UNI-ROYAL(厚声)")
      )
      (libsource (lib "easyedapro") (part "1206W4F4701T5E"))
    )
    (comp (ref "R52")
      (value "68R")
      (footprint "easyedapro:R1206")
      (description "电阻类型:厚膜电阻;阻值:4.7kΩ;精度:±1%;功率:250mW;最大工作电压:200V;温度系数:±100ppm/°C;")
      (fields
        (field (name "Manufacturer Part") "1206W4F4701T5E")
        (field (name "Manufacturer") "UNI-ROYAL(厚声)")
      )
      (libsource (lib "easyedapro") (part "1206W4F4701T5E"))
    )
    (comp (ref "R55")
      (value "68R")
      (footprint "easyedapro:R1206")
      (description "电阻类型:厚膜电阻;阻值:4.7kΩ;精度:±1%;功率:250mW;最大工作电压:200V;温度系数:±100ppm/°C;")
      (fields
        (field (name "Manufacturer Part") "1206W4F4701T5E")
        (field (name "Manufacturer") "UNI-ROYAL(厚声)")
      )
      (libsource (lib "easyedapro") (part "1206W4F4701T5E"))
    )
    (comp (ref "SW1")
      (value "5.8 ZSGT")
      (footprint "easyedapro:SW-TH_5.8ZSGT")
      (description "电路结构:双刀双掷;自锁/无锁:自锁;安装方式:直插;触点电流:110mA;额定电压 (DC):30V;带灯:不带;作用力:1.5N;机械寿命:10万次;")
      (fields (field (name "Manufacturer") "SHOU HAN(首韩)"))
      (libsource (lib "easyedapro") (part "5.8 ZSGT"))
    )
    (comp (ref "U15")
      (value "LCKFB-DKX-STM32F103C8T6")
      (footprint "easyedapro:CONN-TH_L53.3-W22.9_STM32F103C8T6-CARD")
      (fields (field (name "Manufacturer") "立创开发板"))
      (libsource (lib "easyedapro") (part "LCKFB-DKX-STM32F103C8T6"))
    )
  )
  (nets
    (net (code "1") (name "3V3") (class "Default")
      (node (ref "C24") (pin "1") (pinfunction "1_1") (pintype "unspecified"))
      (node (ref "C29") (pin "1") (pinfunction "1_1") (pintype "input"))
      (node (ref "C30") (pin "2") (pinfunction "2_2") (pintype "unspecified"))
      (node (ref "D15") (pin "1") (pinfunction "A_1") (pintype "unspecified"))
      (node (ref "R51") (pin "2") (pinfunction "2_2") (pintype "input"))
      (node (ref "R52") (pin "1") (pinfunction "1_1") (pintype "input"))
      (node (ref "U13") (pin "3") (pinfunction "VOUT_3") (pintype "unspecified"))
      (node (ref "U9") (pin "8") (pinfunction "VCC+_8") (pintype "unspecified"))
    )
    (net (code "2") (name "A0") (class "Default")
      (node (ref "U1") (pin "11") (pinfunction "A0_11") (pintype "unspecified"))
      (node (ref "U15") (pin "7") (pinfunction "PA10_7") (pintype "unspecified"))
    )
    (net (code "3") (name "A1") (class "Default")
      (node (ref "U1") (pin "10") (pinfunction "A1_10") (pintype "unspecified"))
      (node (ref "U15") (pin "6") (pinfunction "PA9_6") (pintype "unspecified"))
    )
    (net (code "4") (name "A2") (class "Default")
      (node (ref "U1") (pin "9") (pinfunction "A2_9") (pintype "unspecified"))
      (node (ref "U15") (pin "5") (pinfunction "PA8_5") (pintype "unspecified"))
    )
    (net (code "5") (name "ADC") (class "Default")
      (node (ref "R38") (pin "2") (pinfunction "2_2") (pintype "input"))
      (node (ref "R39") (pin "2") (pinfunction "2_2") (pintype "input"))
      (node (ref "R42") (pin "1") (pinfunction "1_1") (pintype "input"))
      (node (ref "R45") (pin "1") (pinfunction "1_1") (pintype "input"))
      (node (ref "U1") (pin "3") (pinfunction "Z_3") (pintype "unspecified"))
    )
    (net (code "6") (name "AGND") (class "Default")
      (node (ref "C18") (pin "1") (pinfunction "1_1") (pintype "unspecified"))
      (node (ref "C2") (pin "2") (pinfunction "2_2") (pintype "unspecified"))
      (node (ref "C24") (pin "2") (pinfunction "2_2") (pintype "unspecified"))
      (node (ref "C25") (pin "2") (pinfunction "2_2") (pintype "unspecified"))
      (node (ref "RN4") (pin "1") (pinfunction "1_1") (pintype "input"))
      (node (ref "RN4") (pin "2") (pinfunction "2_2") (pintype "input"))
      (node (ref "RN4") (pin "3") (pinfunction "3_3") (pintype "input"))
      (node (ref "RN4") (pin "4") (pinfunction "4_4") (pintype "input"))
      (node (ref "U12") (pin "2") (pinfunction "2_2") (pintype "unspecified"))
      (node (ref "U6") (pin "6") (pinfunction "VIN-_6") (pintype "unspecified"))
      (node (ref "U8") (pin "4") (pinfunction "VCC-/GND_4") (pintype "unspecified"))
      (node (ref "U9") (pin "4") (pinfunction "VCC-/GND_4") (pintype "unspecified"))
    )
    (net (code "7") (name "ALM") (class "Default")
      (node (ref "D6") (pin "1") (pinfunction "A_1") (pintype "unspecified"))
      (node (ref "R46") (pin "2") (pinfunction "2_2") (pintype "input"))
      (node (ref "R48") (pin "2") (pinfunction "2_2") (pintype "input"))
      (node (ref "U15") (pin "30") (pinfunction "PA5_30") (pintype "unspecified"))
      (node (ref "U7") (pin "4") (pinfunction "OUT_4") (pintype "unspecified"))
    )
    (net (code "8") (name "CS") (class "Default")
      (node (ref "H2") (pin "1") (pinfunction "1_1") (pintype "unspecified"))
      (node (ref "U15") (pin "14") (pinfunction "PB6_14") (pintype "unspecified"))
    )
    (net (code "9") (name "DC") (class "Default")
      (node (ref "H2") (pin "3") (pinfunction "3_3") (pintype "unspecified"))
      (node (ref "U15") (pin "15") (pinfunction "PB7_15") (pintype "unspecified"))
    )
    (net (code "10") (name "GND") (class "Default")
      (node (ref "BUZZER1") (pin "2") (pinfunction "2_2") (pintype "unspecified"))
      (node (ref "C31") (pin "2") (pinfunction "2_2") (pintype "unspecified"))
      (node (ref "H1") (pin "3") (pinfunction "3_3") (pintype "unspecified"))
      (node (ref "SW1") (pin "1") (pinfunction "1_1") (pintype "unspecified"))
      (node (ref "U15") (pin "19") (pinfunction "GND_19") (pintype "unspecified"))
    )
    (net (code "11") (name "IO1") (class "Default")
      (node (ref "H2") (pin "7") (pinfunction "7_7") (pintype "unspecified"))
      (node (ref "U15") (pin "34") (pinfunction "PB1_34") (pintype "unspecified"))
    )
    (net (code "12") (name "IO2") (class "Default")
      (node (ref "H2") (pin "5") (pinfunction "5_5") (pintype "unspecified"))
      (node (ref "U15") (pin "33") (pinfunction "PB0_33") (pintype "unspecified"))
    )
    (net (code "13") (name "K1") (class "Default")
      (node (ref "H2") (pin "8") (pinfunction "8_8") (pintype "unspecified"))
      (node (ref "U15") (pin "26") (pinfunction "PA1_26") (pintype "unspecified"))
    )
    (net (code "14") (name "K2") (class "Default")
      (node (ref "H2") (pin "6") (pinfunction "6_6") (pintype "unspecified"))
      (node (ref "U15") (pin "27") (pinfunction "PA2_27") (pintype "unspecified"))
    )
    (net (code "15") (name "K3") (class "Default")
      (node (ref "H2") (pin "4") (pinfunction "4_4") (pintype "unspecified"))
      (node (ref "U15") (pin "28") (pinfunction "PA3_28") (pintype "unspecified"))
    )
    (net (code "16") (name "K4") (class "Default")
      (node (ref "H2") (pin "2") (pinfunction "2_2") (pintype "unspecified"))
      (node (ref "U15") (pin "29") (pinfunction "PA4_29") (pintype "unspecified"))
    )
    (net (code "17") (name "MISO") (class "Default")
      (node (ref "H1") (pin "4") (pinfunction "4_4") (pintype "unspecified"))
      (node (ref "U15") (pin "12") (pinfunction "PB4_12") (pintype "unspecified"))
    )
    (net (code "18") (name "MOSI") (class "Default")
      (node (ref "H1") (pin "2") (pinfunction "2_2") (pintype "unspecified"))
      (node (ref "U15") (pin "13") (pinfunction "PB5_13") (pintype "unspecified"))
    )
    (net (code "19") (name "NSS") (class "Default")
      (node (ref "H1") (pin "8") (pinfunction "8_8") (pintype "unspecified"))
      (node (ref "U15") (pin "10") (pinfunction "PA15_10") (pintype "unspecified"))
    )
    (net (code "20") (name "Net-(BUZZER1-Pad1)") (class "Default")
      (node (ref "BUZZER1") (pin "1") (pinfunction "1_1") (pintype "unspecified"))
      (node (ref "R55") (pin "1") (pinfunction "1_1") (pintype "input"))
    )
    (net (code "21") (name "Net-(C32-Pad1)") (class "Default")
      (node (ref "C32") (pin "1") (pinfunction "1_1") (pintype "unspecified"))
      (node (ref "SW1") (pin "5") (pinfunction "5_5") (pintype "unspecified"))
      (node (ref "SW1") (pin "6") (pinfunction "6_6") (pintype "unspecified"))
      (node (ref "U15") (pin "38") (pinfunction "+3.3V_38") (pintype "unspecified"))
    )
    (net (code "22") (name "Net-(D5-A)") (class "Default")
      (node (ref "D5") (pin "1") (pinfunction "A_1") (pintype "unspecified"))
      (node (ref "R35") (pin "2") (pinfunction "2_2") (pintype "input"))
    )
    (net (code "23") (name "Net-(D5-K)") (class "Default")
      (node (ref "C19") (pin "1") (pinfunction "1_1") (pintype "unspecified"))
      (node (ref "D5") (pin "2") (pinfunction "K_2") (pintype "unspecified"))
      (node (ref "D6") (pin "2") (pinfunction "K_2") (pintype "unspecified"))
      (node (ref "Q4") (pin "3") (pinfunction "C_3") (pintype "unspecified"))
      (node (ref "U7") (pin "3") (pinfunction "IN+_3") (pintype "unspecified"))
    )
    (net (code "24") (name "Net-(D7-A)") (class "Default")
      (node (ref "D7") (pin "2") (pinfunction "A_2") (pintype "unspecified"))
      (node (ref "RN3") (pin "2") (pinfunction "2_2") (pintype "input"))
      (node (ref "RN3") (pin "3") (pinfunction "3_3") (pintype "input"))
      (node (ref "RN4") (pin "6") (pinfunction "6_6") (pintype "input"))
      (node (ref "RN4") (pin "7") (pinfunction "7_7") (pintype "input"))
      (node (ref "U8") (pin "3") (pinfunction "IN1+_3") (pintype "unspecified"))
    )
    (net (code "25") (name "Net-(D8-A)") (class "Default")
      (node (ref "D8") (pin "2") (pinfunction "A_2") (pintype "unspecified"))
      (node (ref "RN3") (pin "4") (pinfunction "4_4") (pintype "input"))
      (node (ref "RN4") (pin "5") (pinfunction "5_5") (pintype "input"))
      (node (ref "U8") (pin "5") (pinfunction "IN2+_5") (pintype "unspecified"))
    )
    (net (code "26") (name "Net-(D13-A)") (class "Default")
      (node (ref "D13") (pin "1") (pinfunction "A_1") (pintype "unspecified"))
      (node (ref "Q1") (pin "3") (pinfunction "C_3") (pintype "unspecified"))
      (node (ref "RLY1") (pin "4") (pinfunction "4_4") (pintype "input"))
    )
    (net (code "27") (name "Net-(D13-K)") (class "Default")
      (node (ref "D13") (pin "2") (pinfunction "K_2") (pintype "unspecified"))
      (node (ref "Q3") (pin "3") (pinfunction "C_3") (pintype "unspecified"))
      (node (ref "RLY1") (pin "1") (pinfunction "1_1") (pintype "input"))
    )
    (net (code "28") (name "Net-(D17-K)") (class "Default")
      (node (ref "C18") (pin "2") (pinfunction "2_2") (pintype "unspecified"))
      (node (ref "D17") (pin "2") (pinfunction "K_2") (pintype "unspecified"))
      (node (ref "D18") (pin "1") (pinfunction "A_1") (pintype "unspecified"))
      (node (ref "R35") (pin "1") (pinfunction "1_1") (pintype "input"))
      (node (ref "R45") (pin "2") (pinfunction "2_2") (pintype "input"))
      (node (ref "U6") (pin "1") (pinfunction "VIN+_1") (pintype "unspecified"))
    )
    (net (code "29") (name "Net-(F1-Pad2)") (class "Default")
      (node (ref "F1") (pin "2") (pinfunction "2_2") (pintype "unspecified"))
      (node (ref "RLY1") (pin "5") (pinfunction "5_5") (pintype "input"))
    )
    (net (code "30") (name "Net-(H1-Pad1)") (class "Default")
      (node (ref "H1") (pin "1") (pinfunction "1_1") (pintype "unspecified"))
      (node (ref "SW1") (pin "4") (pinfunction "4_4") (pintype "unspecified"))
    )
    (net (code "31") (name "Net-(LED1-+)") (class "Default")
      (node (ref "LED1") (pin "1") (pinfunction "+_1") (pintype "unspecified"))
      (node (ref "R34") (pin "2") (pinfunction "2_2") (pintype "input"))
    )
    (net (code "32") (name "Net-(Q1-B)") (class "Default")
      (node (ref "Q1") (pin "2") (pinfunction "B_2") (pintype "unspecified"))
      (node (ref "R47") (pin "2") (pinfunction "2_2") (pintype "input"))
    )
    (net (code "33") (name "Net-(Q3-B)") (class "Default")
      (node (ref "Q3") (pin "2") (pinfunction "B_2") (pintype "unspecified"))
      (node (ref "R48") (pin "1") (pinfunction "1_1") (pintype "input"))
    )
    (net (code "34") (name "Net-(Q4-B)") (class "Default")
      (node (ref "Q4") (pin "2") (pinfunction "B_2") (pintype "unspecified"))
      (node (ref "R49") (pin "2") (pinfunction "2_2") (pintype "input"))
    )
    (net (code "35") (name "Net-(R54-Pad1)") (class "Default")
      (node (ref "R54") (pin "1") (pinfunction "1_1") (pintype "unspecified"))
      (node (ref "RN1") (pin "7") (pinfunction "7_7") (pintype "input"))
      (node (ref "RN1") (pin "8") (pinfunction "8_8") (pintype "input"))
      (node (ref "U10") (pin "2") (pinfunction "2_2") (pintype "unspecified"))
    )
    (net (code "36") (name "Net-(RN1-Pad2)") (class "Default")
      (node (ref "RN1") (pin "2") (pinfunction "2_2") (pintype "input"))
      (node (ref "RN1") (pin "5") (pinfunction "5_5") (pintype "input"))
      (node (ref "RN1") (pin "6") (pinfunction "6_6") (pintype "input"))
      (node (ref "RN2") (pin "3") (pinfunction "3_3") (pintype "input"))
      (node (ref "U11") (pin "2") (pinfunction "2_2") (pintype "unspecified"))
    )
    (net (code "37") (name "Net-(RN1-Pad3)") (class "Default")
      (node (ref "RN1") (pin "3") (pinfunction "3_3") (pintype "input"))
      (node (ref "RN2") (pin "6") (pinfunction "6_6") (pintype "input"))
      (node (ref "RN2") (pin "7") (pinfunction "7_7") (pintype "input"))
    )
    (net (code "38") (name "Net-(RN1-Pad4)") (class "Default")
      (node (ref "RN1") (pin "4") (pinfunction "4_4") (pintype "input"))
      (node (ref "RN2") (pin "5") (pinfunction "5_5") (pintype "input"))
    )
    (net (code "39") (name "Net-(RN2-Pad1)") (class "Default")
      (node (ref "RN2") (pin "1") (pinfunction "1_1") (pintype "input"))
      (node (ref "RN3") (pin "8") (pinfunction "8_8") (pintype "input"))
    )
    (net (code "40") (name "Net-(RN2-Pad2)") (class "Default")
      (node (ref "RN2") (pin "2") (pinfunction "2_2") (pintype "input"))
      (node (ref "RN3") (pin "6") (pinfunction "6_6") (pintype "input"))
      (node (ref "RN3") (pin "7") (pinfunction "7_7") (pintype "input"))
    )
    (net (code "41") (name "Net-(RN2-Pad4)") (class "Default")
      (node (ref "RN2") (pin "4") (pinfunction "4_4") (pintype "input"))
      (node (ref "RN3") (pin "5") (pinfunction "5_5") (pintype "input"))
    )
    (net (code "42") (name "Net-(RN3-Pad1)") (class "Default")
      (node (ref "RN3") (pin "1") (pinfunction "1_1") (pintype "input"))
      (node (ref "RN4") (pin "8") (pinfunction "8_8") (pintype "input"))
    )
    (net (code "43") (name "Net-(U7-IN-)") (class "Default")
      (node (ref "C26") (pin "1") (pinfunction "1_1") (pintype "unspecified"))
      (node (ref "R43") (pin "2") (pinfunction "2_2") (pintype "input"))
      (node (ref "R44") (pin "1") (pinfunction "1_1") (pintype "input"))
      (node (ref "U7") (pin "1") (pinfunction "IN-_1") (pintype "unspecified"))
    )
    (net (code "44") (name "Net-(U8A-IN1-)") (class "Default")
      (node (ref "R38") (pin "1") (pinfunction "1_1") (pintype "input"))
      (node (ref "U8") (pin "2") (pinfunction "IN1-_2") (pintype "unspecified"))
    )
    (net (code "45") (name "Net-(U8B-IN2-)") (class "Default")
      (node (ref "R39") (pin "1") (pinfunction "1_1") (pintype "input"))
      (node (ref "U8") (pin "6") (pinfunction "IN2-_6") (pintype "unspecified"))
    )
    (net (code "46") (name "Net-(U9A-IN1+)") (class "Default")
      (node (ref "RN1") (pin "1") (pinfunction "1_1") (pintype "input"))
      (node (ref "RN2") (pin "8") (pinfunction "8_8") (pintype "input"))
      (node (ref "U9") (pin "3") (pinfunction "IN1+_3") (pintype "unspecified"))
    )
    (net (code "47") (name "Net-(U9A-IN1-)") (class "Default")
      (node (ref "R42") (pin "2") (pinfunction "2_2") (pintype "input"))
      (node (ref "U9") (pin "2") (pinfunction "IN1-_2") (pintype "unspecified"))
    )
    (net (code "48") (name "Net-(U9B-IN2+)") (class "Default")
      (node (ref "R58") (pin "1") (pinfunction "1_1") (pintype "input"))
      (node (ref "U9") (pin "5") (pinfunction "IN2+_5") (pintype "unspecified"))
    )
    (net (code "49") (name "Net-(U9B-IN2-)") (class "Default")
      (node (ref "C33") (pin "2") (pinfunction "2_2") (pintype "unspecified"))
      (node (ref "R56") (pin "2") (pinfunction "2_2") (pintype "input"))
      (node (ref "R57") (pin "1") (pinfunction "1_1") (pintype "input"))
      (node (ref "U9") (pin "6") (pinfunction "IN2-_6") (pintype "unspecified"))
    )
    (net (code "50") (name "Net-(U9B-OUT2)") (class "Default")
      (node (ref "C34") (pin "2") (pinfunction "2_2") (pintype "unspecified"))
      (node (ref "R58") (pin "2") (pinfunction "2_2") (pintype "input"))
      (node (ref "R59") (pin "2") (pinfunction "2_2") (pintype "input"))
      (node (ref "U12") (pin "1") (pinfunction "1_1") (pintype "unspecified"))
      (node (ref "U9") (pin "7") (pinfunction "OUT2_7") (pintype "output"))
    )
    (net (code "51") (name "Net-(U14-G)") (class "Default")
      (node (ref "R27") (pin "3") (pinfunction "3_3") (pintype "unspecified"))
      (node (ref "R50") (pin "2") (pinfunction "2_2") (pintype "input"))
      (node (ref "RN5") (pin "5") (pinfunction "5_5") (pintype "input"))
      (node (ref "U14") (pin "2") (pinfunction "G_2") (pintype "unspecified"))
    )
    (net (code "52") (name "Net-(U14-S)") (class "Default")
      (node (ref "R27") (pin "1") (pinfunction "1_1") (pintype "unspecified"))
      (node (ref "R27") (pin "2") (pinfunction "2_2") (pintype "unspecified"))
      (node (ref "R50") (pin "1") (pinfunction "1_1") (pintype "input"))
      (node (ref "U14") (pin "3") (pinfunction "S_3") (pintype "unspecified"))
    )
    (net (code "53") (name "Net-(U15-PA12)") (class "Default")
      (node (ref "R55") (pin "2") (pinfunction "2_2") (pintype "input"))
      (node (ref "U15") (pin "9") (pinfunction "PA12_9") (pintype "unspecified"))
    )
    (net (code "54") (name "Net-(U15-RESET)") (class "Default")
      (node (ref "C32") (pin "2") (pinfunction "2_2") (pintype "unspecified"))
      (node (ref "SW1") (pin "2") (pinfunction "2_2") (pintype "unspecified"))
      (node (ref "SW1") (pin "3") (pinfunction "3_3") (pintype "unspecified"))
      (node (ref "U15") (pin "37") (pinfunction "RESET_37") (pintype "unspecified"))
    )
    (net (code "55") (name "REF1") (class "Default")
      (node (ref "C21") (pin "2") (pinfunction "2_2") (pintype "unspecified"))
      (node (ref "RN5") (pin "1") (pinfunction "1_1") (pintype "input"))
      (node (ref "RN5") (pin "2") (pinfunction "2_2") (pintype "input"))
      (node (ref "U1") (pin "2") (pinfunction "Y6_2") (pintype "unspecified"))
    )
    (net (code "56") (name "REF2") (class "Default")
      (node (ref "C22") (pin "2") (pinfunction "2_2") (pintype "unspecified"))
      (node (ref "RN5") (pin "6") (pinfunction "6_6") (pintype "input"))
      (node (ref "RN5") (pin "7") (pinfunction "7_7") (pintype "input"))
      (node (ref "U1") (pin "4") (pinfunction "Y7_4") (pintype "unspecified"))
    )
    (net (code "57") (name "REF3") (class "Default")
      (node (ref "C23") (pin "2") (pinfunction "2_2") (pintype "unspecified"))
      (node (ref "RN5") (pin "3") (pinfunction "3_3") (pintype "input"))
      (node (ref "RN5") (pin "4") (pinfunction "4_4") (pintype "input"))
      (node (ref "U1") (pin "5") (pinfunction "Y5_5") (pintype "unspecified"))
    )
    (net (code "58") (name "RST") (class "Default")
      (node (ref "R49") (pin "1") (pinfunction "1_1") (pintype "input"))
      (node (ref "U15") (pin "31") (pinfunction "PA6_31") (pintype "unspecified"))
    )
    (net (code "59") (name "SCK") (class "Default")
      (node (ref "H1") (pin "6") (pinfunction "6_6") (pintype "unspecified"))
      (node (ref "U15") (pin "11") (pinfunction "PB3_11") (pintype "unspecified"))
    )
    (net (code "60") (name "SCL") (class "Default")
      (node (ref "H1") (pin "7") (pinfunction "7_7") (pintype "unspecified"))
      (node (ref "R51") (pin "1") (pinfunction "1_1") (pintype "input"))
      (node (ref "U15") (pin "16") (pinfunction "PB8_16") (pintype "unspecified"))
      (node (ref "U6") (pin "3") (pinfunction "SCL_3") (pintype "unspecified"))
    )
    (net (code "61") (name "SDA") (class "Default")
      (node (ref "H1") (pin "5") (pinfunction "5_5") (pintype "unspecified"))
      (node (ref "R52") (pin "2") (pinfunction "2_2") (pintype "input"))
      (node (ref "U15") (pin "17") (pinfunction "PB9_17") (pintype "unspecified"))
      (node (ref "U6") (pin "4") (pinfunction "SDA_4") (pintype "unspecified"))
    )
    (net (code "62") (name "SW1") (class "Default")
      (node (ref "R47") (pin "1") (pinfunction "1_1") (pintype "input"))
      (node (ref "U15") (pin "32") (pinfunction "PA7_32") (pintype "unspecified"))
    )
    (net (code "63") (name "U0") (class "Default")
      (node (ref "F1") (pin "1") (pinfunction "1_1") (pintype "unspecified"))
    )
    (net (code "64") (name "U0.2V") (class "Default")
      (node (ref "C2") (pin "1") (pinfunction "1_1") (pintype "unspecified"))
      (node (ref "U1") (pin "1") (pinfunction "Y4_1") (pintype "unspecified"))
    )
    (net (code "65") (name "U0H") (class "Default")
      (node (ref "RLY1") (pin "3") (pinfunction "3_3") (pintype "input"))
      (node (ref "U11") (pin "1") (pinfunction "1_1") (pintype "unspecified"))
    )
    (net (code "66") (name "U0L") (class "Default")
      (node (ref "RLY1") (pin "2") (pinfunction "2_2") (pintype "input"))
      (node (ref "U10") (pin "1") (pinfunction "1_1") (pintype "unspecified"))
    )
    (net (code "67") (name "U1KV") (class "Default")
      (node (ref "C6") (pin "1") (pinfunction "1_1") (pintype "unspecified"))
      (node (ref "U1") (pin "12") (pinfunction "Y3_12") (pintype "unspecified"))
      (node (ref "U8") (pin "1") (pinfunction "OUT1_1") (pintype "output"))
    )
    (net (code "68") (name "U2V") (class "Default")
      (node (ref "C3") (pin "1") (pinfunction "1_1") (pintype "unspecified"))
      (node (ref "D14") (pin "2") (pinfunction "K_2") (pintype "unspecified"))
      (node (ref "D16") (pin "1") (pinfunction "A_1") (pintype "unspecified"))
      (node (ref "R54") (pin "2") (pinfunction "2_2") (pintype "unspecified"))
      (node (ref "U1") (pin "15") (pinfunction "Y2_15") (pintype "unspecified"))
    )
    (net (code "69") (name "U18V") (class "Default")
      (node (ref "C4") (pin "1") (pinfunction "1_1") (pintype "unspecified"))
      (node (ref "U1") (pin "14") (pinfunction "Y1_14") (pintype "unspecified"))
      (node (ref "U9") (pin "1") (pinfunction "OUT1_1") (pintype "output"))
    )
    (net (code "70") (name "U200V") (class "Default")
      (node (ref "C5") (pin "1") (pinfunction "1_1") (pintype "unspecified"))
      (node (ref "U1") (pin "13") (pinfunction "Y0_13") (pintype "unspecified"))
      (node (ref "U8") (pin "7") (pinfunction "OUT2_7") (pintype "output"))
    )
    (net (code "71") (name "VCC") (class "Default")
      (node (ref "C20") (pin "2") (pinfunction "2_2") (pintype "unspecified"))
      (node (ref "C25") (pin "1") (pinfunction "1_1") (pintype "unspecified"))
      (node (ref "C27") (pin "2") (pinfunction "2_2") (pintype "unspecified"))
      (node (ref "C28") (pin "1") (pinfunction "1_1") (pintype "input"))
      (node (ref "C31") (pin "1") (pinfunction "1_1") (pintype "unspecified"))
      (node (ref "C7") (pin "1") (pinfunction "1_1") (pintype "unspecified"))
      (node (ref "CN1") (pin "2") (pinfunction "2_2") (pintype "unspecified"))
      (node (ref "D15") (pin "2") (pinfunction "K_2") (pintype "unspecified"))
      (node (ref "D16") (pin "2") (pinfunction "K_2") (pintype "unspecified"))
      (node (ref "D18") (pin "2") (pinfunction "K_2") (pintype "unspecified"))
      (node (ref "D7") (pin "1") (pinfunction "C_1") (pintype "unspecified"))
      (node (ref "D8") (pin "1") (pinfunction "C_1") (pintype "unspecified"))
      (node (ref "Q3") (pin "1") (pinfunction "E_1") (pintype "unspecified"))
      (node (ref "R34") (pin "1") (pinfunction "1_1") (pintype "input"))
      (node (ref "R44") (pin "2") (pinfunction "2_2") (pintype "input"))
      (node (ref "R46") (pin "1") (pinfunction "1_1") (pintype "input"))
      (node (ref "R56") (pin "1") (pinfunction "1_1") (pintype "input"))
      (node (ref "U1") (pin "16") (pinfunction "VDD_16") (pintype "unspecified"))
      (node (ref "U13") (pin "2") (pinfunction "VIN_2") (pintype "unspecified"))
      (node (ref "U14") (pin "1") (pinfunction "D_1") (pintype "unspecified"))
      (node (ref "U15") (pin "18") (pinfunction "+5V_18") (pintype "unspecified"))
      (node (ref "U6") (pin "5") (pinfunction "VDD_5") (pintype "unspecified"))
      (node (ref "U7") (pin "5") (pinfunction "VCC_5") (pintype "unspecified"))
      (node (ref "U8") (pin "8") (pinfunction "VCC+_8") (pintype "unspecified"))
    )
    (net (code "72") (name "VEE") (class "Default")
      (node (ref "C19") (pin "2") (pinfunction "2_2") (pintype "unspecified"))
      (node (ref "C20") (pin "1") (pinfunction "1_1") (pintype "unspecified"))
      (node (ref "C21") (pin "1") (pinfunction "1_1") (pintype "unspecified"))
      (node (ref "C22") (pin "1") (pinfunction "1_1") (pintype "unspecified"))
      (node (ref "C23") (pin "1") (pinfunction "1_1") (pintype "unspecified"))
      (node (ref "C26") (pin "2") (pinfunction "2_2") (pintype "unspecified"))
      (node (ref "C27") (pin "1") (pinfunction "1_1") (pintype "unspecified"))
      (node (ref "C28") (pin "2") (pinfunction "2_2") (pintype "input"))
      (node (ref "C29") (pin "2") (pinfunction "2_2") (pintype "input"))
      (node (ref "C3") (pin "2") (pinfunction "2_2") (pintype "unspecified"))
      (node (ref "C30") (pin "1") (pinfunction "1_1") (pintype "unspecified"))
      (node (ref "C33") (pin "1") (pinfunction "1_1") (pintype "unspecified"))
      (node (ref "C34") (pin "1") (pinfunction "1_1") (pintype "unspecified"))
      (node (ref "C4") (pin "2") (pinfunction "2_2") (pintype "unspecified"))
      (node (ref "C5") (pin "2") (pinfunction "2_2") (pintype "unspecified"))
      (node (ref "C6") (pin "2") (pinfunction "2_2") (pintype "unspecified"))
      (node (ref "C7") (pin "2") (pinfunction "2_2") (pintype "unspecified"))
      (node (ref "CN1") (pin "1") (pinfunction "1_1") (pintype "unspecified"))
      (node (ref "D14") (pin "1") (pinfunction "A_1") (pintype "unspecified"))
      (node (ref "D17") (pin "1") (pinfunction "A_1") (pintype "unspecified"))
      (node (ref "LED1") (pin "2") (pinfunction "-_2") (pintype "unspecified"))
      (node (ref "Q1") (pin "1") (pinfunction "E_1") (pintype "unspecified"))
      (node (ref "Q4") (pin "1") (pinfunction "E_1") (pintype "unspecified"))
      (node (ref "R43") (pin "1") (pinfunction "1_1") (pintype "input"))
      (node (ref "R57") (pin "2") (pinfunction "2_2") (pintype "input"))
      (node (ref "R59") (pin "1") (pinfunction "1_1") (pintype "input"))
      (node (ref "RN5") (pin "8") (pinfunction "8_8") (pintype "input"))
      (node (ref "U1") (pin "6") (pinfunction "E#_6") (pintype "unspecified"))
      (node (ref "U1") (pin "7") (pinfunction "VEE_7") (pintype "unspecified"))
      (node (ref "U1") (pin "8") (pinfunction "VSS_8") (pintype "unspecified"))
      (node (ref "U13") (pin "1") (pinfunction "GND_1") (pintype "unspecified"))
      (node (ref "U6") (pin "2") (pinfunction "GND_2") (pintype "unspecified"))
      (node (ref "U7") (pin "2") (pinfunction "VCC-/GND_2") (pintype "unspecified"))
    )
    (net (code "73") (name "unconnected-(U15-+3.3V-Pad20)") (class "Default")
      (node (ref "U15") (pin "20") (pinfunction "+3.3V_20") (pintype "unspecified"))
    )
    (net (code "74") (name "unconnected-(U15-GND-Pad39)") (class "Default")
      (node (ref "U15") (pin "39") (pinfunction "GND_39") (pintype "unspecified"))
    )
    (net (code "75") (name "unconnected-(U15-GND-Pad40)") (class "Default")
      (node (ref "U15") (pin "40") (pinfunction "GND_40") (pintype "unspecified"))
    )
    (net (code "76") (name "unconnected-(U15-PA0-Pad25)") (class "Default")
      (node (ref "U15") (pin "25") (pinfunction "PA0_25") (pintype "unspecified"))
    )
    (net (code "77") (name "unconnected-(U15-PA11-Pad8)") (class "Default")
      (node (ref "U15") (pin "8") (pinfunction "PA11_8") (pintype "unspecified"))
    )
    (net (code "78") (name "unconnected-(U15-PB10-Pad35)") (class "Default")
      (node (ref "U15") (pin "35") (pinfunction "PB10_35") (pintype "unspecified"))
    )
    (net (code "79") (name "unconnected-(U15-PB11-Pad36)") (class "Default")
      (node (ref "U15") (pin "36") (pinfunction "PB11_36") (pintype "unspecified"))
    )
    (net (code "80") (name "unconnected-(U15-PB12-Pad1)") (class "Default")
      (node (ref "U15") (pin "1") (pinfunction "PB12_1") (pintype "unspecified"))
    )
    (net (code "81") (name "unconnected-(U15-PB13-Pad2)") (class "Default")
      (node (ref "U15") (pin "2") (pinfunction "PB13_2") (pintype "unspecified"))
    )
    (net (code "82") (name "unconnected-(U15-PB14-Pad3)") (class "Default")
      (node (ref "U15") (pin "3") (pinfunction "PB14_3") (pintype "unspecified"))
    )
    (net (code "83") (name "unconnected-(U15-PB15-Pad4)") (class "Default")
      (node (ref "U15") (pin "4") (pinfunction "PB15_4") (pintype "unspecified"))
    )
    (net (code "84") (name "unconnected-(U15-PC13-Pad22)") (class "Default")
      (node (ref "U15") (pin "22") (pinfunction "PC13_22") (pintype "unspecified"))
    )
    (net (code "85") (name "unconnected-(U15-PC14-Pad23)") (class "Default")
      (node (ref "U15") (pin "23") (pinfunction "PC14_23") (pintype "unspecified"))
    )
    (net (code "86") (name "unconnected-(U15-PC15-Pad24)") (class "Default")
      (node (ref "U15") (pin "24") (pinfunction "PC15_24") (pintype "unspecified"))
    )
    (net (code "87") (name "unconnected-(U15-VBAT-Pad21)") (class "Default")
      (node (ref "U15") (pin "21") (pinfunction "VBAT_21") (pintype "unspecified"))
    )
  )
)
